# Controller.net
KiCad netlist of a schematic drawn in Altium Designer
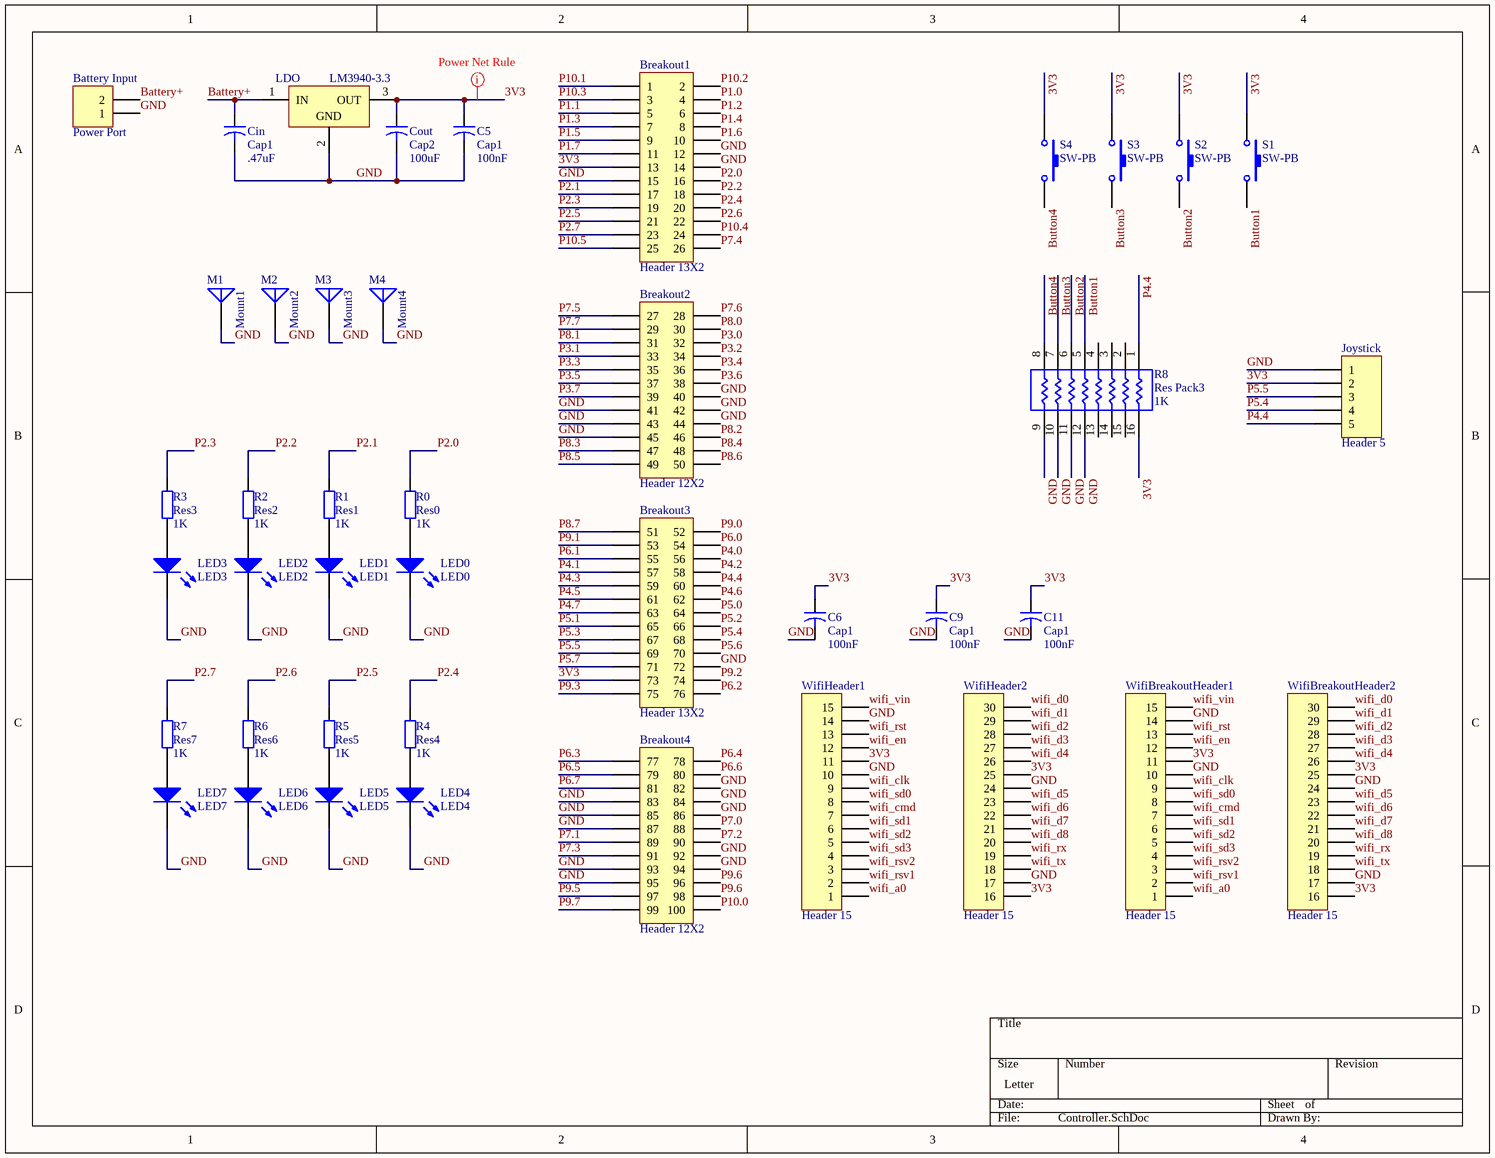
[diagram p0: Controller.SchDoc]

(export (version "E")
  (design (tool "Eeschema 10.0.6"))
  (components
    (comp (ref "Battery Input")
      (value "Power Port")
      (footprint "CON2screw")
      (libsource (lib "ECE LIB new") (part "Power"))
    )
    (comp (ref "Breakout1")
      (value "Header 13X2")
      (footprint "HDR2X13")
      (description "Header, 13-Pin, Dual row")
      (fields (field (name "PUBLISHER") "Altium Limited"))
      (libsource (lib "Miscellaneous Connectors") (part "Header 13X2"))
    )
    (comp (ref "Breakout2")
      (value "Header 12X2")
      (footprint "HDR2X12")
      (description "Header, 12-Pin, Dual row")
      (fields (field (name "PUBLISHER") "Altium Limited"))
      (libsource (lib "Miscellaneous Connectors") (part "Header 12X2"))
    )
    (comp (ref "Breakout3")
      (value "Header 13X2")
      (footprint "HDR2X13")
      (description "Header, 13-Pin, Dual row")
      (fields (field (name "PUBLISHER") "Altium Limited"))
      (libsource (lib "Miscellaneous Connectors") (part "Header 13X2"))
    )
    (comp (ref "Breakout4")
      (value "Header 12X2")
      (footprint "HDR2X12")
      (description "Header, 12-Pin, Dual row")
      (fields (field (name "PUBLISHER") "Altium Limited"))
      (libsource (lib "Miscellaneous Connectors") (part "Header 12X2"))
    )
    (comp (ref "C5")
      (value "Cap1")
      (footprint "CAPR5-4X5")
      (description "Capacitor")
      (fields (field (name "ALTIUM_VALUE") "100nF") (field (name "PUBLISHER") "Altium Limited"))
      (libsource (lib "Miscellaneous Devices") (part "Cap2"))
    )
    (comp (ref "C6")
      (value "Cap1")
      (footprint "CAPR5-4X5")
      (description "Capacitor")
      (fields (field (name "ALTIUM_VALUE") "100nF") (field (name "PUBLISHER") "Altium Limited"))
      (libsource (lib "Miscellaneous Devices") (part "Cap2"))
    )
    (comp (ref "C9")
      (value "Cap1")
      (footprint "CAPR5-4X5")
      (description "Capacitor")
      (fields (field (name "ALTIUM_VALUE") "100nF") (field (name "PUBLISHER") "Altium Limited"))
      (libsource (lib "Miscellaneous Devices") (part "Cap2"))
    )
    (comp (ref "C11")
      (value "Cap1")
      (footprint "CAPR5-4X5")
      (description "Capacitor")
      (fields (field (name "ALTIUM_VALUE") "100nF") (field (name "PUBLISHER") "Altium Limited"))
      (libsource (lib "Miscellaneous Devices") (part "Cap2"))
    )
    (comp (ref "Cin")
      (value "Cap1")
      (footprint "CAPR5-4X5")
      (description "Capacitor")
      (fields (field (name "ALTIUM_VALUE") ".47uF") (field (name "PUBLISHER") "Altium Limited"))
      (libsource (lib "Miscellaneous Devices") (part "Cap2"))
    )
    (comp (ref "Cout")
      (value "Cap2")
      (footprint "CAPR5-4X5")
      (description "Capacitor")
      (fields (field (name "ALTIUM_VALUE") "100uF") (field (name "PUBLISHER") "Altium Limited"))
      (libsource (lib "Miscellaneous Devices") (part "Cap2"))
    )
    (comp (ref "Joystick")
      (value "Header 5")
      (footprint "HDR1X5")
      (description "Header, 5-Pin")
      (fields (field (name "PUBLISHER") "Altium Limited"))
      (libsource (lib "Miscellaneous Connectors") (part "Header 5"))
    )
    (comp (ref "LDO")
      (value "LM3940-3.3")
      (footprint "T03B")
      (description "1A Low Dropout Regulator, 3-pin TO-220")
      (fields
        (field (name "PARTNUMBER") "LM2940CT-3.3")
        (field (name "MANUFACTURER") "National Semiconductor")
      )
      (libsource (lib "ECE LIB new") (part "LM2940CT-5.0"))
    )
    (comp (ref "LED0")
      (value "LED0")
      (footprint "PIN2")
      (description "Typical INFRARED GaAs LED")
      (fields (field (name "PUBLISHER") "Altium Limited"))
      (libsource (lib "Miscellaneous Devices") (part "LED0"))
    )
    (comp (ref "LED1")
      (value "LED1")
      (footprint "PIN2")
      (description "Typical INFRARED GaAs LED")
      (fields (field (name "PUBLISHER") "Altium Limited"))
      (libsource (lib "Miscellaneous Devices") (part "LED0"))
    )
    (comp (ref "LED2")
      (value "LED2")
      (footprint "PIN2")
      (description "Typical INFRARED GaAs LED")
      (fields (field (name "PUBLISHER") "Altium Limited"))
      (libsource (lib "Miscellaneous Devices") (part "LED0"))
    )
    (comp (ref "LED3")
      (value "LED3")
      (footprint "PIN2")
      (description "Typical INFRARED GaAs LED")
      (fields (field (name "PUBLISHER") "Altium Limited"))
      (libsource (lib "Miscellaneous Devices") (part "LED0"))
    )
    (comp (ref "LED4")
      (value "LED4")
      (footprint "PIN2")
      (description "Typical INFRARED GaAs LED")
      (fields (field (name "PUBLISHER") "Altium Limited"))
      (libsource (lib "Miscellaneous Devices") (part "LED0"))
    )
    (comp (ref "LED5")
      (value "LED5")
      (footprint "PIN2")
      (description "Typical INFRARED GaAs LED")
      (fields (field (name "PUBLISHER") "Altium Limited"))
      (libsource (lib "Miscellaneous Devices") (part "LED0"))
    )
    (comp (ref "LED6")
      (value "LED6")
      (footprint "PIN2")
      (description "Typical INFRARED GaAs LED")
      (fields (field (name "PUBLISHER") "Altium Limited"))
      (libsource (lib "Miscellaneous Devices") (part "LED0"))
    )
    (comp (ref "LED7")
      (value "LED7")
      (footprint "PIN2")
      (description "Typical INFRARED GaAs LED")
      (fields (field (name "PUBLISHER") "Altium Limited"))
      (libsource (lib "Miscellaneous Devices") (part "LED0"))
    )
    (comp (ref "M1")
      (value "Mount1")
      (footprint "PIN1")
      (description "Generic Antenna")
      (fields (field (name "PUBLISHER") "Altium Limited"))
      (libsource (lib "Miscellaneous Devices") (part "Antenna"))
    )
    (comp (ref "M2")
      (value "Mount2")
      (footprint "PIN1")
      (description "Generic Antenna")
      (fields (field (name "PUBLISHER") "Altium Limited"))
      (libsource (lib "Miscellaneous Devices") (part "Antenna"))
    )
    (comp (ref "M3")
      (value "Mount3")
      (footprint "PIN1")
      (description "Generic Antenna")
      (fields (field (name "PUBLISHER") "Altium Limited"))
      (libsource (lib "Miscellaneous Devices") (part "Antenna"))
    )
    (comp (ref "M4")
      (value "Mount4")
      (footprint "PIN1")
      (description "Generic Antenna")
      (fields (field (name "PUBLISHER") "Altium Limited"))
      (libsource (lib "Miscellaneous Devices") (part "Antenna"))
    )
    (comp (ref "R0")
      (value "Res0")
      (footprint "AXIAL-0.4")
      (description "Resistor")
      (fields (field (name "ALTIUM_VALUE") "1K") (field (name "PUBLISHER") "Altium Limited"))
      (libsource (lib "Miscellaneous Devices") (part "Res2"))
    )
    (comp (ref "R1")
      (value "Res1")
      (footprint "AXIAL-0.4")
      (description "Resistor")
      (fields (field (name "ALTIUM_VALUE") "1K") (field (name "PUBLISHER") "Altium Limited"))
      (libsource (lib "Miscellaneous Devices") (part "Res2"))
    )
    (comp (ref "R2")
      (value "Res2")
      (footprint "AXIAL-0.4")
      (description "Resistor")
      (fields (field (name "ALTIUM_VALUE") "1K") (field (name "PUBLISHER") "Altium Limited"))
      (libsource (lib "Miscellaneous Devices") (part "Res2"))
    )
    (comp (ref "R3")
      (value "Res3")
      (footprint "AXIAL-0.4")
      (description "Resistor")
      (fields (field (name "ALTIUM_VALUE") "1K") (field (name "PUBLISHER") "Altium Limited"))
      (libsource (lib "Miscellaneous Devices") (part "Res2"))
    )
    (comp (ref "R4")
      (value "Res4")
      (footprint "AXIAL-0.4")
      (description "Resistor")
      (fields (field (name "ALTIUM_VALUE") "1K") (field (name "PUBLISHER") "Altium Limited"))
      (libsource (lib "Miscellaneous Devices") (part "Res2"))
    )
    (comp (ref "R5")
      (value "Res5")
      (footprint "AXIAL-0.4")
      (description "Resistor")
      (fields (field (name "ALTIUM_VALUE") "1K") (field (name "PUBLISHER") "Altium Limited"))
      (libsource (lib "Miscellaneous Devices") (part "Res2"))
    )
    (comp (ref "R6")
      (value "Res6")
      (footprint "AXIAL-0.4")
      (description "Resistor")
      (fields (field (name "ALTIUM_VALUE") "1K") (field (name "PUBLISHER") "Altium Limited"))
      (libsource (lib "Miscellaneous Devices") (part "Res2"))
    )
    (comp (ref "R7")
      (value "Res7")
      (footprint "AXIAL-0.4")
      (description "Resistor")
      (fields (field (name "ALTIUM_VALUE") "1K") (field (name "PUBLISHER") "Altium Limited"))
      (libsource (lib "Miscellaneous Devices") (part "Res2"))
    )
    (comp (ref "R8")
      (value "Res Pack3")
      (footprint "DIP-16")
      (description "Isolated Resistor Network")
      (fields (field (name "ALTIUM_VALUE") "1K") (field (name "PUBLISHER") "Altium Limited"))
      (libsource (lib "Miscellaneous Devices") (part "Res Pack3"))
    )
    (comp (ref "S1")
      (value "SW-PB")
      (footprint "SW PB")
      (description "DIGIKEY SW400-ND")
      (fields (field (name "PUBLISHER") "Altium Limited"))
      (libsource (lib "ECE LIB new") (part "SW-PB_2"))
    )
    (comp (ref "S2")
      (value "SW-PB")
      (footprint "SW PB")
      (description "DIGIKEY SW400-ND")
      (fields (field (name "PUBLISHER") "Altium Limited"))
      (libsource (lib "ECE LIB new") (part "SW-PB_2"))
    )
    (comp (ref "S3")
      (value "SW-PB")
      (footprint "SW PB")
      (description "DIGIKEY SW400-ND")
      (fields (field (name "PUBLISHER") "Altium Limited"))
      (libsource (lib "ECE LIB new") (part "SW-PB_2"))
    )
    (comp (ref "S4")
      (value "SW-PB")
      (footprint "SW PB")
      (description "DIGIKEY SW400-ND")
      (fields (field (name "PUBLISHER") "Altium Limited"))
      (libsource (lib "ECE LIB new") (part "SW-PB_2"))
    )
    (comp (ref "WifiBreakoutHeader1")
      (value "Header 15")
      (footprint "HDR1X15")
      (description "Header, 15-Pin")
      (fields (field (name "PUBLISHER") "Altium Limited"))
      (libsource (lib "Miscellaneous Connectors") (part "Header 15"))
    )
    (comp (ref "WifiBreakoutHeader2")
      (value "Header 15")
      (footprint "HDR1X15")
      (description "Header, 15-Pin")
      (fields (field (name "PUBLISHER") "Altium Limited"))
      (libsource (lib "Miscellaneous Connectors") (part "Header 15"))
    )
    (comp (ref "WifiHeader1")
      (value "Header 15")
      (footprint "HDR1X15")
      (description "Header, 15-Pin")
      (fields (field (name "PUBLISHER") "Altium Limited"))
      (libsource (lib "Miscellaneous Connectors") (part "Header 15"))
    )
    (comp (ref "WifiHeader2")
      (value "Header 15")
      (footprint "HDR1X15")
      (description "Header, 15-Pin")
      (fields (field (name "PUBLISHER") "Altium Limited"))
      (libsource (lib "Miscellaneous Connectors") (part "Header 15"))
    )
  )
  (nets
    (net (code "1") (name "/3V3") (class "Default")
      (node (ref "Breakout1") (pin "13") (pinfunction "13_13") (pintype "passive"))
      (node (ref "Breakout3") (pin "23") (pinfunction "23_23") (pintype "passive"))
      (node (ref "C11") (pin "1") (pinfunction "1_1") (pintype "passive"))
      (node (ref "C5") (pin "1") (pinfunction "1_1") (pintype "passive"))
      (node (ref "C6") (pin "1") (pinfunction "1_1") (pintype "passive"))
      (node (ref "C9") (pin "1") (pinfunction "1_1") (pintype "passive"))
      (node (ref "Cout") (pin "1") (pinfunction "1_1") (pintype "passive"))
      (node (ref "Joystick") (pin "2") (pinfunction "2_2") (pintype "passive"))
      (node (ref "LDO") (pin "3") (pinfunction "OUT_3") (pintype "power_in"))
      (node (ref "R8") (pin "16") (pinfunction "16_16") (pintype "passive"))
      (node (ref "S1") (pin "1") (pinfunction "1_1") (pintype "passive"))
      (node (ref "S2") (pin "1") (pinfunction "1_1") (pintype "passive"))
      (node (ref "S3") (pin "1") (pinfunction "1_1") (pintype "passive"))
      (node (ref "S4") (pin "1") (pinfunction "1_1") (pintype "passive"))
      (node (ref "WifiBreakoutHeader1") (pin "11") (pinfunction "26_11") (pintype "passive"))
      (node (ref "WifiBreakoutHeader2") (pin "1") (pinfunction "16_1") (pintype "passive"))
      (node (ref "WifiBreakoutHeader2") (pin "10") (pinfunction "25_10") (pintype "passive"))
      (node (ref "WifiHeader1") (pin "11") (pinfunction "26_11") (pintype "passive"))
      (node (ref "WifiHeader2") (pin "1") (pinfunction "16_1") (pintype "passive"))
      (node (ref "WifiHeader2") (pin "10") (pinfunction "25_10") (pintype "passive"))
    )
    (net (code "2") (name "/Battery+") (class "Default")
      (node (ref "Battery Input") (pin "2") (pinfunction "2_2") (pintype "passive"))
      (node (ref "Cin") (pin "1") (pinfunction "1_1") (pintype "passive"))
      (node (ref "LDO") (pin "1") (pinfunction "IN_1") (pintype "power_in"))
    )
    (net (code "3") (name "/Button1") (class "Default")
      (node (ref "R8") (pin "5") (pinfunction "5_5") (pintype "passive"))
      (node (ref "S1") (pin "2") (pinfunction "2_2") (pintype "passive"))
    )
    (net (code "4") (name "/Button2") (class "Default")
      (node (ref "R8") (pin "6") (pinfunction "6_6") (pintype "passive"))
      (node (ref "S2") (pin "2") (pinfunction "2_2") (pintype "passive"))
    )
    (net (code "5") (name "/Button3") (class "Default")
      (node (ref "R8") (pin "7") (pinfunction "7_7") (pintype "passive"))
      (node (ref "S3") (pin "2") (pinfunction "2_2") (pintype "passive"))
    )
    (net (code "6") (name "/Button4") (class "Default")
      (node (ref "R8") (pin "8") (pinfunction "8_8") (pintype "passive"))
      (node (ref "S4") (pin "2") (pinfunction "2_2") (pintype "passive"))
    )
    (net (code "7") (name "/GND") (class "Default")
      (node (ref "Battery Input") (pin "1") (pinfunction "1_1") (pintype "passive"))
      (node (ref "Breakout1") (pin "12") (pinfunction "12_12") (pintype "passive"))
      (node (ref "Breakout1") (pin "14") (pinfunction "14_14") (pintype "passive"))
      (node (ref "Breakout1") (pin "15") (pinfunction "15_15") (pintype "passive"))
      (node (ref "Breakout2") (pin "14") (pinfunction "40_14") (pintype "passive"))
      (node (ref "Breakout2") (pin "15") (pinfunction "41_15") (pintype "passive"))
      (node (ref "Breakout2") (pin "16") (pinfunction "42_16") (pintype "passive"))
      (node (ref "Breakout2") (pin "17") (pinfunction "43_17") (pintype "passive"))
      (node (ref "Breakout2") (pin "18") (pinfunction "44_18") (pintype "passive"))
      (node (ref "Breakout2") (pin "19") (pinfunction "45_19") (pintype "passive"))
      (node (ref "Breakout3") (pin "22") (pinfunction "22_22") (pintype "passive"))
      (node (ref "Breakout4") (pin "10") (pinfunction "36_10") (pintype "passive"))
      (node (ref "Breakout4") (pin "11") (pinfunction "37_11") (pintype "passive"))
      (node (ref "Breakout4") (pin "16") (pinfunction "42_16") (pintype "passive"))
      (node (ref "Breakout4") (pin "17") (pinfunction "43_17") (pintype "passive"))
      (node (ref "Breakout4") (pin "18") (pinfunction "44_18") (pintype "passive"))
      (node (ref "Breakout4") (pin "19") (pinfunction "45_19") (pintype "passive"))
      (node (ref "Breakout4") (pin "6") (pinfunction "32_6") (pintype "passive"))
      (node (ref "Breakout4") (pin "7") (pinfunction "33_7") (pintype "passive"))
      (node (ref "Breakout4") (pin "8") (pinfunction "34_8") (pintype "passive"))
      (node (ref "Breakout4") (pin "9") (pinfunction "35_9") (pintype "passive"))
      (node (ref "C11") (pin "2") (pinfunction "2_2") (pintype "passive"))
      (node (ref "C5") (pin "2") (pinfunction "2_2") (pintype "passive"))
      (node (ref "C6") (pin "2") (pinfunction "2_2") (pintype "passive"))
      (node (ref "C9") (pin "2") (pinfunction "2_2") (pintype "passive"))
      (node (ref "Cin") (pin "2") (pinfunction "2_2") (pintype "passive"))
      (node (ref "Cout") (pin "2") (pinfunction "2_2") (pintype "passive"))
      (node (ref "Joystick") (pin "1") (pinfunction "1_1") (pintype "passive"))
      (node (ref "LDO") (pin "2") (pinfunction "GND_2") (pintype "power_in"))
      (node (ref "LED0") (pin "2") (pinfunction "K_2") (pintype "passive"))
      (node (ref "LED1") (pin "2") (pinfunction "K_2") (pintype "passive"))
      (node (ref "LED2") (pin "2") (pinfunction "K_2") (pintype "passive"))
      (node (ref "LED3") (pin "2") (pinfunction "K_2") (pintype "passive"))
      (node (ref "LED4") (pin "2") (pinfunction "K_2") (pintype "passive"))
      (node (ref "LED5") (pin "2") (pinfunction "K_2") (pintype "passive"))
      (node (ref "LED6") (pin "2") (pinfunction "K_2") (pintype "passive"))
      (node (ref "LED7") (pin "2") (pinfunction "K_2") (pintype "passive"))
      (node (ref "M1") (pin "1") (pinfunction "A_1") (pintype "passive"))
      (node (ref "M2") (pin "1") (pinfunction "A_1") (pintype "passive"))
      (node (ref "M3") (pin "1") (pinfunction "A_1") (pintype "passive"))
      (node (ref "M4") (pin "1") (pinfunction "A_1") (pintype "passive"))
      (node (ref "R8") (pin "10") (pinfunction "10_10") (pintype "passive"))
      (node (ref "R8") (pin "11") (pinfunction "11_11") (pintype "passive"))
      (node (ref "R8") (pin "12") (pinfunction "12_12") (pintype "passive"))
      (node (ref "R8") (pin "9") (pinfunction "9_9") (pintype "passive"))
      (node (ref "WifiBreakoutHeader1") (pin "10") (pinfunction "25_10") (pintype "passive"))
      (node (ref "WifiBreakoutHeader1") (pin "14") (pinfunction "29_14") (pintype "passive"))
      (node (ref "WifiBreakoutHeader2") (pin "2") (pinfunction "17_2") (pintype "passive"))
      (node (ref "WifiBreakoutHeader2") (pin "9") (pinfunction "24_9") (pintype "passive"))
      (node (ref "WifiHeader1") (pin "10") (pinfunction "25_10") (pintype "passive"))
      (node (ref "WifiHeader1") (pin "14") (pinfunction "29_14") (pintype "passive"))
      (node (ref "WifiHeader2") (pin "2") (pinfunction "17_2") (pintype "passive"))
      (node (ref "WifiHeader2") (pin "9") (pinfunction "24_9") (pintype "passive"))
    )
    (net (code "8") (name "/P1.0") (class "Default")
      (node (ref "Breakout1") (pin "4") (pinfunction "4_4") (pintype "passive"))
    )
    (net (code "9") (name "/P1.1") (class "Default")
      (node (ref "Breakout1") (pin "5") (pinfunction "5_5") (pintype "passive"))
    )
    (net (code "10") (name "/P1.2") (class "Default")
      (node (ref "Breakout1") (pin "6") (pinfunction "6_6") (pintype "passive"))
    )
    (net (code "11") (name "/P1.3") (class "Default")
      (node (ref "Breakout1") (pin "7") (pinfunction "7_7") (pintype "passive"))
    )
    (net (code "12") (name "/P1.4") (class "Default")
      (node (ref "Breakout1") (pin "8") (pinfunction "8_8") (pintype "passive"))
    )
    (net (code "13") (name "/P1.5") (class "Default")
      (node (ref "Breakout1") (pin "9") (pinfunction "9_9") (pintype "passive"))
    )
    (net (code "14") (name "/P1.6") (class "Default")
      (node (ref "Breakout1") (pin "10") (pinfunction "10_10") (pintype "passive"))
    )
    (net (code "15") (name "/P1.7") (class "Default")
      (node (ref "Breakout1") (pin "11") (pinfunction "11_11") (pintype "passive"))
    )
    (net (code "16") (name "/P2.0") (class "Default")
      (node (ref "Breakout1") (pin "16") (pinfunction "16_16") (pintype "passive"))
      (node (ref "R0") (pin "2") (pinfunction "2_2") (pintype "passive"))
    )
    (net (code "17") (name "/P2.1") (class "Default")
      (node (ref "Breakout1") (pin "17") (pinfunction "17_17") (pintype "passive"))
      (node (ref "R1") (pin "2") (pinfunction "2_2") (pintype "passive"))
    )
    (net (code "18") (name "/P2.2") (class "Default")
      (node (ref "Breakout1") (pin "18") (pinfunction "18_18") (pintype "passive"))
      (node (ref "R2") (pin "2") (pinfunction "2_2") (pintype "passive"))
    )
    (net (code "19") (name "/P2.3") (class "Default")
      (node (ref "Breakout1") (pin "19") (pinfunction "19_19") (pintype "passive"))
      (node (ref "R3") (pin "2") (pinfunction "2_2") (pintype "passive"))
    )
    (net (code "20") (name "/P2.4") (class "Default")
      (node (ref "Breakout1") (pin "20") (pinfunction "20_20") (pintype "passive"))
      (node (ref "R4") (pin "2") (pinfunction "2_2") (pintype "passive"))
    )
    (net (code "21") (name "/P2.5") (class "Default")
      (node (ref "Breakout1") (pin "21") (pinfunction "21_21") (pintype "passive"))
      (node (ref "R5") (pin "2") (pinfunction "2_2") (pintype "passive"))
    )
    (net (code "22") (name "/P2.6") (class "Default")
      (node (ref "Breakout1") (pin "22") (pinfunction "22_22") (pintype "passive"))
      (node (ref "R6") (pin "2") (pinfunction "2_2") (pintype "passive"))
    )
    (net (code "23") (name "/P2.7") (class "Default")
      (node (ref "Breakout1") (pin "23") (pinfunction "23_23") (pintype "passive"))
      (node (ref "R7") (pin "2") (pinfunction "2_2") (pintype "passive"))
    )
    (net (code "24") (name "/P3.0") (class "Default")
      (node (ref "Breakout2") (pin "6") (pinfunction "32_6") (pintype "passive"))
    )
    (net (code "25") (name "/P3.1") (class "Default")
      (node (ref "Breakout2") (pin "7") (pinfunction "33_7") (pintype "passive"))
    )
    (net (code "26") (name "/P3.2") (class "Default")
      (node (ref "Breakout2") (pin "8") (pinfunction "34_8") (pintype "passive"))
    )
    (net (code "27") (name "/P3.3") (class "Default")
      (node (ref "Breakout2") (pin "9") (pinfunction "35_9") (pintype "passive"))
    )
    (net (code "28") (name "/P3.4") (class "Default")
      (node (ref "Breakout2") (pin "10") (pinfunction "36_10") (pintype "passive"))
    )
    (net (code "29") (name "/P3.5") (class "Default")
      (node (ref "Breakout2") (pin "11") (pinfunction "37_11") (pintype "passive"))
    )
    (net (code "30") (name "/P3.6") (class "Default")
      (node (ref "Breakout2") (pin "12") (pinfunction "38_12") (pintype "passive"))
    )
    (net (code "31") (name "/P3.7") (class "Default")
      (node (ref "Breakout2") (pin "13") (pinfunction "39_13") (pintype "passive"))
    )
    (net (code "32") (name "/P4.0") (class "Default")
      (node (ref "Breakout3") (pin "6") (pinfunction "6_6") (pintype "passive"))
    )
    (net (code "33") (name "/P4.1") (class "Default")
      (node (ref "Breakout3") (pin "7") (pinfunction "7_7") (pintype "passive"))
    )
    (net (code "34") (name "/P4.2") (class "Default")
      (node (ref "Breakout3") (pin "8") (pinfunction "8_8") (pintype "passive"))
    )
    (net (code "35") (name "/P4.3") (class "Default")
      (node (ref "Breakout3") (pin "9") (pinfunction "9_9") (pintype "passive"))
    )
    (net (code "36") (name "/P4.4") (class "Default")
      (node (ref "Breakout3") (pin "10") (pinfunction "10_10") (pintype "passive"))
      (node (ref "Joystick") (pin "5") (pinfunction "5_5") (pintype "passive"))
      (node (ref "R8") (pin "1") (pinfunction "1_1") (pintype "passive"))
    )
    (net (code "37") (name "/P4.5") (class "Default")
      (node (ref "Breakout3") (pin "11") (pinfunction "11_11") (pintype "passive"))
    )
    (net (code "38") (name "/P4.6") (class "Default")
      (node (ref "Breakout3") (pin "12") (pinfunction "12_12") (pintype "passive"))
    )
    (net (code "39") (name "/P4.7") (class "Default")
      (node (ref "Breakout3") (pin "13") (pinfunction "13_13") (pintype "passive"))
    )
    (net (code "40") (name "/P5.0") (class "Default")
      (node (ref "Breakout3") (pin "14") (pinfunction "14_14") (pintype "passive"))
    )
    (net (code "41") (name "/P5.1") (class "Default")
      (node (ref "Breakout3") (pin "15") (pinfunction "15_15") (pintype "passive"))
    )
    (net (code "42") (name "/P5.2") (class "Default")
      (node (ref "Breakout3") (pin "16") (pinfunction "16_16") (pintype "passive"))
    )
    (net (code "43") (name "/P5.3") (class "Default")
      (node (ref "Breakout3") (pin "17") (pinfunction "17_17") (pintype "passive"))
    )
    (net (code "44") (name "/P5.4") (class "Default")
      (node (ref "Breakout3") (pin "18") (pinfunction "18_18") (pintype "passive"))
      (node (ref "Joystick") (pin "4") (pinfunction "4_4") (pintype "passive"))
    )
    (net (code "45") (name "/P5.5") (class "Default")
      (node (ref "Breakout3") (pin "19") (pinfunction "19_19") (pintype "passive"))
      (node (ref "Joystick") (pin "3") (pinfunction "3_3") (pintype "passive"))
    )
    (net (code "46") (name "/P5.6") (class "Default")
      (node (ref "Breakout3") (pin "20") (pinfunction "20_20") (pintype "passive"))
    )
    (net (code "47") (name "/P5.7") (class "Default")
      (node (ref "Breakout3") (pin "21") (pinfunction "21_21") (pintype "passive"))
    )
    (net (code "48") (name "/P6.0") (class "Default")
      (node (ref "Breakout3") (pin "4") (pinfunction "4_4") (pintype "passive"))
    )
    (net (code "49") (name "/P6.1") (class "Default")
      (node (ref "Breakout3") (pin "5") (pinfunction "5_5") (pintype "passive"))
    )
    (net (code "50") (name "/P6.2") (class "Default")
      (node (ref "Breakout3") (pin "26") (pinfunction "26_26") (pintype "passive"))
    )
    (net (code "51") (name "/P6.3") (class "Default")
      (node (ref "Breakout4") (pin "1") (pinfunction "27_1") (pintype "passive"))
    )
    (net (code "52") (name "/P6.4") (class "Default")
      (node (ref "Breakout4") (pin "2") (pinfunction "28_2") (pintype "passive"))
    )
    (net (code "53") (name "/P6.5") (class "Default")
      (node (ref "Breakout4") (pin "3") (pinfunction "29_3") (pintype "passive"))
    )
    (net (code "54") (name "/P6.6") (class "Default")
      (node (ref "Breakout4") (pin "4") (pinfunction "30_4") (pintype "passive"))
    )
    (net (code "55") (name "/P6.7") (class "Default")
      (node (ref "Breakout4") (pin "5") (pinfunction "31_5") (pintype "passive"))
    )
    (net (code "56") (name "/P7.0") (class "Default")
      (node (ref "Breakout4") (pin "12") (pinfunction "38_12") (pintype "passive"))
    )
    (net (code "57") (name "/P7.1") (class "Default")
      (node (ref "Breakout4") (pin "13") (pinfunction "39_13") (pintype "passive"))
    )
    (net (code "58") (name "/P7.2") (class "Default")
      (node (ref "Breakout4") (pin "14") (pinfunction "40_14") (pintype "passive"))
    )
    (net (code "59") (name "/P7.3") (class "Default")
      (node (ref "Breakout4") (pin "15") (pinfunction "41_15") (pintype "passive"))
    )
    (net (code "60") (name "/P7.4") (class "Default")
      (node (ref "Breakout1") (pin "26") (pinfunction "26_26") (pintype "passive"))
    )
    (net (code "61") (name "/P7.5") (class "Default")
      (node (ref "Breakout2") (pin "1") (pinfunction "27_1") (pintype "passive"))
    )
    (net (code "62") (name "/P7.6") (class "Default")
      (node (ref "Breakout2") (pin "2") (pinfunction "28_2") (pintype "passive"))
    )
    (net (code "63") (name "/P7.7") (class "Default")
      (node (ref "Breakout2") (pin "3") (pinfunction "29_3") (pintype "passive"))
    )
    (net (code "64") (name "/P8.0") (class "Default")
      (node (ref "Breakout2") (pin "4") (pinfunction "30_4") (pintype "passive"))
    )
    (net (code "65") (name "/P8.1") (class "Default")
      (node (ref "Breakout2") (pin "5") (pinfunction "31_5") (pintype "passive"))
    )
    (net (code "66") (name "/P8.2") (class "Default")
      (node (ref "Breakout2") (pin "20") (pinfunction "46_20") (pintype "passive"))
    )
    (net (code "67") (name "/P8.3") (class "Default")
      (node (ref "Breakout2") (pin "21") (pinfunction "47_21") (pintype "passive"))
    )
    (net (code "68") (name "/P8.4") (class "Default")
      (node (ref "Breakout2") (pin "22") (pinfunction "48_22") (pintype "passive"))
    )
    (net (code "69") (name "/P8.5") (class "Default")
      (node (ref "Breakout2") (pin "23") (pinfunction "49_23") (pintype "passive"))
    )
    (net (code "70") (name "/P8.6") (class "Default")
      (node (ref "Breakout2") (pin "24") (pinfunction "50_24") (pintype "passive"))
    )
    (net (code "71") (name "/P8.7") (class "Default")
      (node (ref "Breakout3") (pin "1") (pinfunction "1_1") (pintype "passive"))
    )
    (net (code "72") (name "/P9.0") (class "Default")
      (node (ref "Breakout3") (pin "2") (pinfunction "2_2") (pintype "passive"))
    )
    (net (code "73") (name "/P9.1") (class "Default")
      (node (ref "Breakout3") (pin "3") (pinfunction "3_3") (pintype "passive"))
    )
    (net (code "74") (name "/P9.2") (class "Default")
      (node (ref "Breakout3") (pin "24") (pinfunction "24_24") (pintype "passive"))
    )
    (net (code "75") (name "/P9.3") (class "Default")
      (node (ref "Breakout3") (pin "25") (pinfunction "25_25") (pintype "passive"))
    )
    (net (code "76") (name "/P9.5") (class "Default")
      (node (ref "Breakout4") (pin "21") (pinfunction "47_21") (pintype "passive"))
    )
    (net (code "77") (name "/P9.6") (class "Default")
      (node (ref "Breakout4") (pin "20") (pinfunction "46_20") (pintype "passive"))
      (node (ref "Breakout4") (pin "22") (pinfunction "48_22") (pintype "passive"))
    )
    (net (code "78") (name "/P9.7") (class "Default")
      (node (ref "Breakout4") (pin "23") (pinfunction "49_23") (pintype "passive"))
    )
    (net (code "79") (name "/P10.0") (class "Default")
      (node (ref "Breakout4") (pin "24") (pinfunction "50_24") (pintype "passive"))
    )
    (net (code "80") (name "/P10.1") (class "Default")
      (node (ref "Breakout1") (pin "1") (pinfunction "1_1") (pintype "passive"))
    )
    (net (code "81") (name "/P10.2") (class "Default")
      (node (ref "Breakout1") (pin "2") (pinfunction "2_2") (pintype "passive"))
    )
    (net (code "82") (name "/P10.3") (class "Default")
      (node (ref "Breakout1") (pin "3") (pinfunction "3_3") (pintype "passive"))
    )
    (net (code "83") (name "/P10.4") (class "Default")
      (node (ref "Breakout1") (pin "24") (pinfunction "24_24") (pintype "passive"))
    )
    (net (code "84") (name "/P10.5") (class "Default")
      (node (ref "Breakout1") (pin "25") (pinfunction "25_25") (pintype "passive"))
    )
    (net (code "85") (name "/wifi_a0") (class "Default")
      (node (ref "WifiBreakoutHeader1") (pin "1") (pinfunction "16_1") (pintype "passive"))
      (node (ref "WifiHeader1") (pin "1") (pinfunction "16_1") (pintype "passive"))
    )
    (net (code "86") (name "/wifi_clk") (class "Default")
      (node (ref "WifiBreakoutHeader1") (pin "9") (pinfunction "24_9") (pintype "passive"))
      (node (ref "WifiHeader1") (pin "9") (pinfunction "24_9") (pintype "passive"))
    )
    (net (code "87") (name "/wifi_cmd") (class "Default")
      (node (ref "WifiBreakoutHeader1") (pin "7") (pinfunction "22_7") (pintype "passive"))
      (node (ref "WifiHeader1") (pin "7") (pinfunction "22_7") (pintype "passive"))
    )
    (net (code "88") (name "/wifi_d0") (class "Default")
      (node (ref "WifiBreakoutHeader2") (pin "15") (pinfunction "30_15") (pintype "passive"))
      (node (ref "WifiHeader2") (pin "15") (pinfunction "30_15") (pintype "passive"))
    )
    (net (code "89") (name "/wifi_d1") (class "Default")
      (node (ref "WifiBreakoutHeader2") (pin "14") (pinfunction "29_14") (pintype "passive"))
      (node (ref "WifiHeader2") (pin "14") (pinfunction "29_14") (pintype "passive"))
    )
    (net (code "90") (name "/wifi_d2") (class "Default")
      (node (ref "WifiBreakoutHeader2") (pin "13") (pinfunction "28_13") (pintype "passive"))
      (node (ref "WifiHeader2") (pin "13") (pinfunction "28_13") (pintype "passive"))
    )
    (net (code "91") (name "/wifi_d3") (class "Default")
      (node (ref "WifiBreakoutHeader2") (pin "12") (pinfunction "27_12") (pintype "passive"))
      (node (ref "WifiHeader2") (pin "12") (pinfunction "27_12") (pintype "passive"))
    )
    (net (code "92") (name "/wifi_d4") (class "Default")
      (node (ref "WifiBreakoutHeader2") (pin "11") (pinfunction "26_11") (pintype "passive"))
      (node (ref "WifiHeader2") (pin "11") (pinfunction "26_11") (pintype "passive"))
    )
    (net (code "93") (name "/wifi_d5") (class "Default")
      (node (ref "WifiBreakoutHeader2") (pin "8") (pinfunction "23_8") (pintype "passive"))
      (node (ref "WifiHeader2") (pin "8") (pinfunction "23_8") (pintype "passive"))
    )
    (net (code "94") (name "/wifi_d6") (class "Default")
      (node (ref "WifiBreakoutHeader2") (pin "7") (pinfunction "22_7") (pintype "passive"))
      (node (ref "WifiHeader2") (pin "7") (pinfunction "22_7") (pintype "passive"))
    )
    (net (code "95") (name "/wifi_d7") (class "Default")
      (node (ref "WifiBreakoutHeader2") (pin "6") (pinfunction "21_6") (pintype "passive"))
      (node (ref "WifiHeader2") (pin "6") (pinfunction "21_6") (pintype "passive"))
    )
    (net (code "96") (name "/wifi_d8") (class "Default")
      (node (ref "WifiBreakoutHeader2") (pin "5") (pinfunction "20_5") (pintype "passive"))
      (node (ref "WifiHeader2") (pin "5") (pinfunction "20_5") (pintype "passive"))
    )
    (net (code "97") (name "/wifi_en") (class "Default")
      (node (ref "WifiBreakoutHeader1") (pin "12") (pinfunction "27_12") (pintype "passive"))
      (node (ref "WifiHeader1") (pin "12") (pinfunction "27_12") (pintype "passive"))
    )
    (net (code "98") (name "/wifi_rst") (class "Default")
      (node (ref "WifiBreakoutHeader1") (pin "13") (pinfunction "28_13") (pintype "passive"))
      (node (ref "WifiHeader1") (pin "13") (pinfunction "28_13") (pintype "passive"))
    )
    (net (code "99") (name "/wifi_rsv1") (class "Default")
      (node (ref "WifiBreakoutHeader1") (pin "2") (pinfunction "17_2") (pintype "passive"))
      (node (ref "WifiHeader1") (pin "2") (pinfunction "17_2") (pintype "passive"))
    )
    (net (code "100") (name "/wifi_rsv2") (class "Default")
      (node (ref "WifiBreakoutHeader1") (pin "3") (pinfunction "18_3") (pintype "passive"))
      (node (ref "WifiHeader1") (pin "3") (pinfunction "18_3") (pintype "passive"))
    )
    (net (code "101") (name "/wifi_rx") (class "Default")
      (node (ref "WifiBreakoutHeader2") (pin "4") (pinfunction "19_4") (pintype "passive"))
      (node (ref "WifiHeader2") (pin "4") (pinfunction "19_4") (pintype "passive"))
    )
    (net (code "102") (name "/wifi_sd0") (class "Default")
      (node (ref "WifiBreakoutHeader1") (pin "8") (pinfunction "23_8") (pintype "passive"))
      (node (ref "WifiHeader1") (pin "8") (pinfunction "23_8") (pintype "passive"))
    )
    (net (code "103") (name "/wifi_sd1") (class "Default")
      (node (ref "WifiBreakoutHeader1") (pin "6") (pinfunction "21_6") (pintype "passive"))
      (node (ref "WifiHeader1") (pin "6") (pinfunction "21_6") (pintype "passive"))
    )
    (net (code "104") (name "/wifi_sd2") (class "Default")
      (node (ref "WifiBreakoutHeader1") (pin "5") (pinfunction "20_5") (pintype "passive"))
      (node (ref "WifiHeader1") (pin "5") (pinfunction "20_5") (pintype "passive"))
    )
    (net (code "105") (name "/wifi_sd3") (class "Default")
      (node (ref "WifiBreakoutHeader1") (pin "4") (pinfunction "19_4") (pintype "passive"))
      (node (ref "WifiHeader1") (pin "4") (pinfunction "19_4") (pintype "passive"))
    )
    (net (code "106") (name "/wifi_tx") (class "Default")
      (node (ref "WifiBreakoutHeader2") (pin "3") (pinfunction "18_3") (pintype "passive"))
      (node (ref "WifiHeader2") (pin "3") (pinfunction "18_3") (pintype "passive"))
    )
    (net (code "107") (name "/wifi_vin") (class "Default")
      (node (ref "WifiBreakoutHeader1") (pin "15") (pinfunction "30_15") (pintype "passive"))
      (node (ref "WifiHeader1") (pin "15") (pinfunction "30_15") (pintype "passive"))
    )
    (net (code "108") (name "Net-(LED0-A)") (class "Default")
      (node (ref "LED0") (pin "1") (pinfunction "A_1") (pintype "passive"))
      (node (ref "R0") (pin "1") (pinfunction "1_1") (pintype "passive"))
    )
    (net (code "109") (name "Net-(LED1-A)") (class "Default")
      (node (ref "LED1") (pin "1") (pinfunction "A_1") (pintype "passive"))
      (node (ref "R1") (pin "1") (pinfunction "1_1") (pintype "passive"))
    )
    (net (code "110") (name "Net-(LED2-A)") (class "Default")
      (node (ref "LED2") (pin "1") (pinfunction "A_1") (pintype "passive"))
      (node (ref "R2") (pin "1") (pinfunction "1_1") (pintype "passive"))
    )
    (net (code "111") (name "Net-(LED3-A)") (class "Default")
      (node (ref "LED3") (pin "1") (pinfunction "A_1") (pintype "passive"))
      (node (ref "R3") (pin "1") (pinfunction "1_1") (pintype "passive"))
    )
    (net (code "112") (name "Net-(LED4-A)") (class "Default")
      (node (ref "LED4") (pin "1") (pinfunction "A_1") (pintype "passive"))
      (node (ref "R4") (pin "1") (pinfunction "1_1") (pintype "passive"))
    )
    (net (code "113") (name "Net-(LED5-A)") (class "Default")
      (node (ref "LED5") (pin "1") (pinfunction "A_1") (pintype "passive"))
      (node (ref "R5") (pin "1") (pinfunction "1_1") (pintype "passive"))
    )
    (net (code "114") (name "Net-(LED6-A)") (class "Default")
      (node (ref "LED6") (pin "1") (pinfunction "A_1") (pintype "passive"))
      (node (ref "R6") (pin "1") (pinfunction "1_1") (pintype "passive"))
    )
    (net (code "115") (name "Net-(LED7-A)") (class "Default")
      (node (ref "LED7") (pin "1") (pinfunction "A_1") (pintype "passive"))
      (node (ref "R7") (pin "1") (pinfunction "1_1") (pintype "passive"))
    )
    (net (code "116") (name "unconnected-(R8-Pad2)") (class "Default")
      (node (ref "R8") (pin "2") (pinfunction "2_2") (pintype "passive"))
    )
    (net (code "117") (name "unconnected-(R8-Pad3)") (class "Default")
      (node (ref "R8") (pin "3") (pinfunction "3_3") (pintype "passive"))
    )
    (net (code "118") (name "unconnected-(R8-Pad4)") (class "Default")
      (node (ref "R8") (pin "4") (pinfunction "4_4") (pintype "passive"))
    )
    (net (code "119") (name "unconnected-(R8-Pad13)") (class "Default")
      (node (ref "R8") (pin "13") (pinfunction "13_13") (pintype "passive"))
    )
    (net (code "120") (name "unconnected-(R8-Pad14)") (class "Default")
      (node (ref "R8") (pin "14") (pinfunction "14_14") (pintype "passive"))
    )
    (net (code "121") (name "unconnected-(R8-Pad15)") (class "Default")
      (node (ref "R8") (pin "15") (pinfunction "15_15") (pintype "passive"))
    )
  )
)
